# MAin.net
KiCad netlist of a schematic drawn in EAGLE
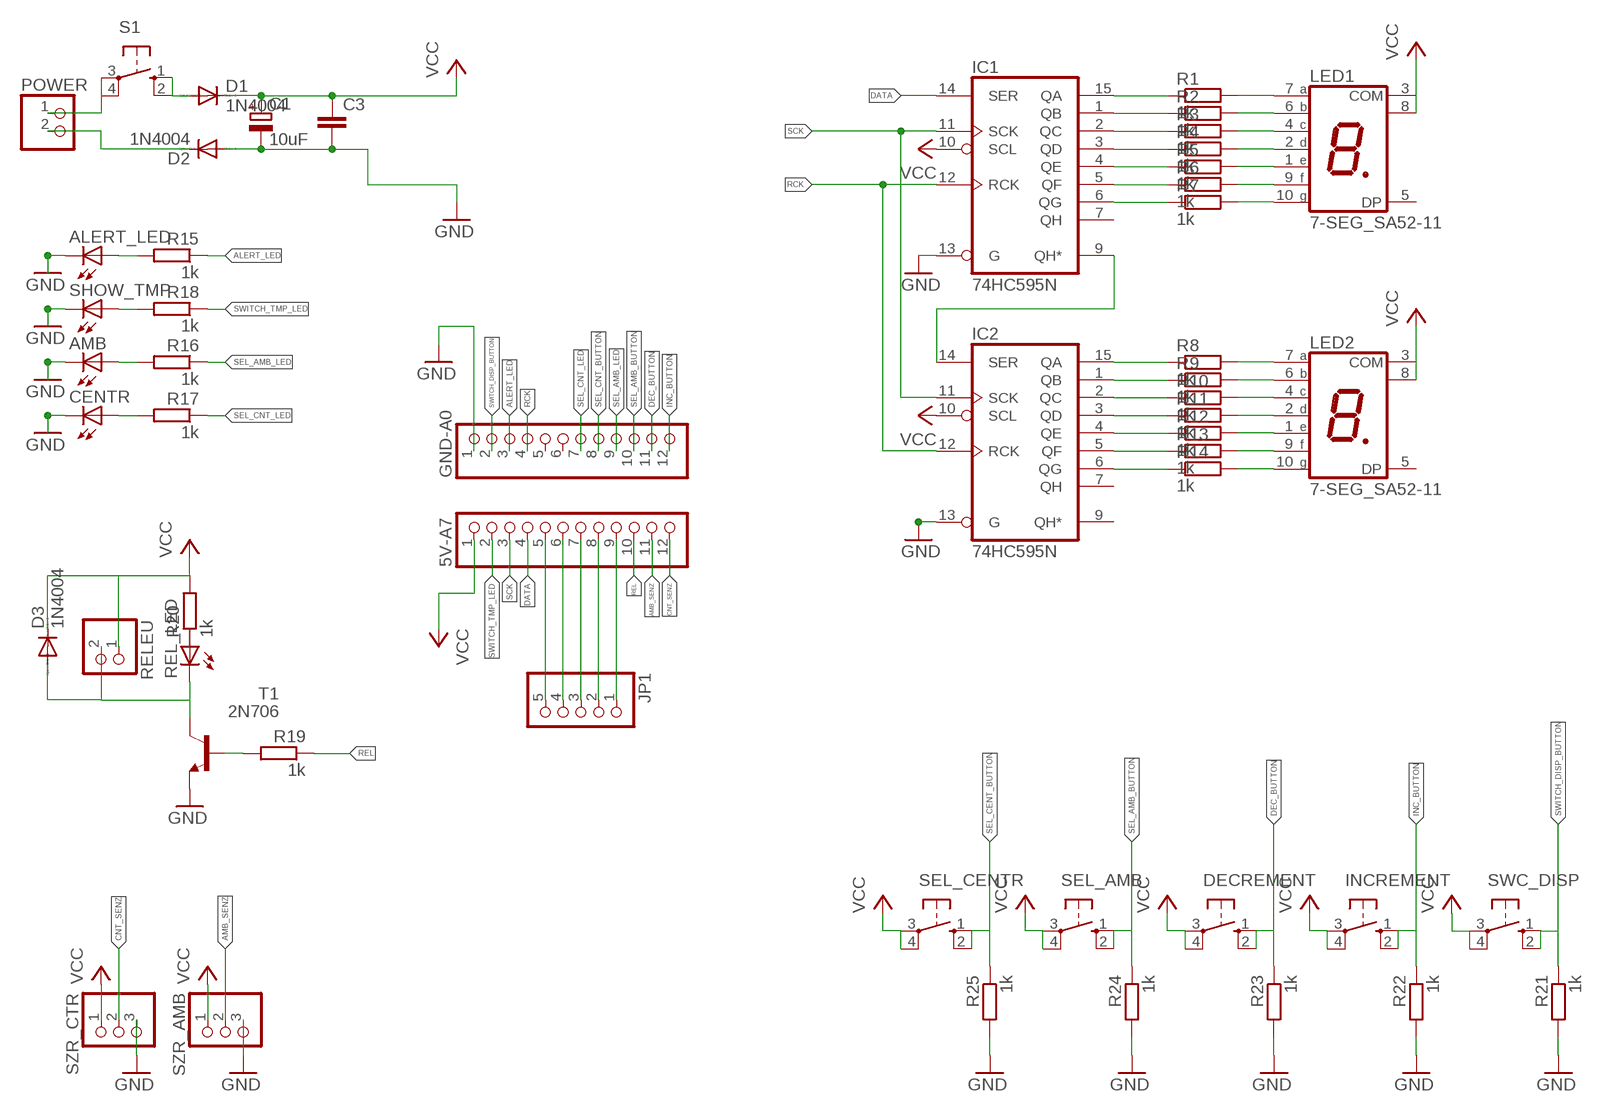
[diagram p0: schematic, sheet 1]

(export (version "E")
  (design (tool "Eeschema 10.0.6"))
  (components
    (comp (ref "5V-A7")
      (value "PINHD-1X12")
      (footprint "eagle-import:1X12")
      (libsource (lib "eagle-import") (part "PINHD-1X12"))
    )
    (comp (ref "ALERT_LED")
      (value "LED5MM")
      (footprint "eagle-import:LED5MM")
      (libsource (lib "eagle-import") (part "LED5MM"))
    )
    (comp (ref "AMB")
      (value "LED5MM")
      (footprint "eagle-import:LED5MM")
      (libsource (lib "eagle-import") (part "LED5MM"))
    )
    (comp (ref "C1")
      (value "10uF")
      (footprint "eagle-import:E2-5")
      (libsource (lib "eagle-import") (part "CPOL-EUE2-5"))
    )
    (comp (ref "C3")
      (value "C-EU025-024X044")
      (footprint "eagle-import:C025-024X044")
      (libsource (lib "eagle-import") (part "C-EU025-024X044"))
    )
    (comp (ref "CENTR")
      (value "LED5MM")
      (footprint "eagle-import:LED5MM")
      (libsource (lib "eagle-import") (part "LED5MM"))
    )
    (comp (ref "D1")
      (value "1N4004")
      (footprint "eagle-import:DO41-10")
      (libsource (lib "eagle-import") (part "1N4004"))
    )
    (comp (ref "D2")
      (value "1N4004")
      (footprint "eagle-import:DO41-10")
      (libsource (lib "eagle-import") (part "1N4004"))
    )
    (comp (ref "D3")
      (value "1N4004")
      (footprint "eagle-import:DO41-10")
      (libsource (lib "eagle-import") (part "1N4004"))
    )
    (comp (ref "DECREMENT")
      (value "40-XX")
      (footprint "eagle-import:B3F-40XX")
      (fields (field (name "MF") "OMRON COMPONENTS USA") (field (name "MPN") "B3F-4000"))
      (libsource (lib "eagle-import") (part "40-XX"))
    )
    (comp (ref "GND-A0")
      (value "PINHD-1X12")
      (footprint "eagle-import:1X12")
      (libsource (lib "eagle-import") (part "PINHD-1X12"))
    )
    (comp (ref "IC1")
      (value "74HC595N")
      (footprint "eagle-import:DIL16")
      (libsource (lib "eagle-import") (part "74595NHC"))
    )
    (comp (ref "IC2")
      (value "74HC595N")
      (footprint "eagle-import:DIL16")
      (libsource (lib "eagle-import") (part "74595NHC"))
    )
    (comp (ref "INCREMENT")
      (value "40-XX")
      (footprint "eagle-import:B3F-40XX")
      (fields (field (name "MF") "OMRON COMPONENTS USA") (field (name "MPN") "B3F-4000"))
      (libsource (lib "eagle-import") (part "40-XX"))
    )
    (comp (ref "JP1")
      (value "PINHD-1X5")
      (footprint "eagle-import:1X05")
      (libsource (lib "eagle-import") (part "PINHD-1X5"))
    )
    (comp (ref "LED1")
      (value "7-SEG_SA52-11")
      (footprint "eagle-import:SA52-11")
      (libsource (lib "eagle-import") (part "7-SEG_SA52-11"))
    )
    (comp (ref "LED2")
      (value "7-SEG_SA52-11")
      (footprint "eagle-import:SA52-11")
      (libsource (lib "eagle-import") (part "7-SEG_SA52-11"))
    )
    (comp (ref "POWER")
      (value "PINHD-1X2")
      (footprint "eagle-import:1X02")
      (libsource (lib "eagle-import") (part "PINHD-1X2"))
    )
    (comp (ref "R1")
      (value "1k")
      (footprint "eagle-import:0309_12")
      (libsource (lib "eagle-import") (part "R-EU_0309/12"))
    )
    (comp (ref "R2")
      (value "1k")
      (footprint "eagle-import:0309_12")
      (libsource (lib "eagle-import") (part "R-EU_0309/12"))
    )
    (comp (ref "R3")
      (value "1k")
      (footprint "eagle-import:0309_12")
      (libsource (lib "eagle-import") (part "R-EU_0309/12"))
    )
    (comp (ref "R4")
      (value "1k")
      (footprint "eagle-import:0309_12")
      (libsource (lib "eagle-import") (part "R-EU_0309/12"))
    )
    (comp (ref "R5")
      (value "1k")
      (footprint "eagle-import:0309_12")
      (libsource (lib "eagle-import") (part "R-EU_0309/12"))
    )
    (comp (ref "R6")
      (value "1k")
      (footprint "eagle-import:0309_12")
      (libsource (lib "eagle-import") (part "R-EU_0309/12"))
    )
    (comp (ref "R7")
      (value "1k")
      (footprint "eagle-import:0309_12")
      (libsource (lib "eagle-import") (part "R-EU_0309/12"))
    )
    (comp (ref "R8")
      (value "1k")
      (footprint "eagle-import:0309_12")
      (libsource (lib "eagle-import") (part "R-EU_0309/12"))
    )
    (comp (ref "R9")
      (value "1k")
      (footprint "eagle-import:0309_12")
      (libsource (lib "eagle-import") (part "R-EU_0309/12"))
    )
    (comp (ref "R10")
      (value "1k")
      (footprint "eagle-import:0309_12")
      (libsource (lib "eagle-import") (part "R-EU_0309/12"))
    )
    (comp (ref "R11")
      (value "1k")
      (footprint "eagle-import:0309_12")
      (libsource (lib "eagle-import") (part "R-EU_0309/12"))
    )
    (comp (ref "R12")
      (value "1k")
      (footprint "eagle-import:0309_12")
      (libsource (lib "eagle-import") (part "R-EU_0309/12"))
    )
    (comp (ref "R13")
      (value "1k")
      (footprint "eagle-import:0309_12")
      (libsource (lib "eagle-import") (part "R-EU_0309/12"))
    )
    (comp (ref "R14")
      (value "1k")
      (footprint "eagle-import:0309_12")
      (libsource (lib "eagle-import") (part "R-EU_0309/12"))
    )
    (comp (ref "R15")
      (value "1k")
      (footprint "eagle-import:0309_12")
      (libsource (lib "eagle-import") (part "R-EU_0309/12"))
    )
    (comp (ref "R16")
      (value "1k")
      (footprint "eagle-import:0309_12")
      (libsource (lib "eagle-import") (part "R-EU_0309/12"))
    )
    (comp (ref "R17")
      (value "1k")
      (footprint "eagle-import:0309_12")
      (libsource (lib "eagle-import") (part "R-EU_0309/12"))
    )
    (comp (ref "R18")
      (value "1k")
      (footprint "eagle-import:0309_12")
      (libsource (lib "eagle-import") (part "R-EU_0309/12"))
    )
    (comp (ref "R19")
      (value "1k")
      (footprint "eagle-import:0309_12")
      (libsource (lib "eagle-import") (part "R-EU_0309/12"))
    )
    (comp (ref "R20")
      (value "1k")
      (footprint "eagle-import:0309_12")
      (libsource (lib "eagle-import") (part "R-EU_0309/12"))
    )
    (comp (ref "R21")
      (value "1k")
      (footprint "eagle-import:0309_12")
      (libsource (lib "eagle-import") (part "R-EU_0309/12"))
    )
    (comp (ref "R22")
      (value "1k")
      (footprint "eagle-import:0309_12")
      (libsource (lib "eagle-import") (part "R-EU_0309/12"))
    )
    (comp (ref "R23")
      (value "1k")
      (footprint "eagle-import:0309_12")
      (libsource (lib "eagle-import") (part "R-EU_0309/12"))
    )
    (comp (ref "R24")
      (value "1k")
      (footprint "eagle-import:0309_12")
      (libsource (lib "eagle-import") (part "R-EU_0309/12"))
    )
    (comp (ref "R25")
      (value "1k")
      (footprint "eagle-import:0309_12")
      (libsource (lib "eagle-import") (part "R-EU_0309/12"))
    )
    (comp (ref "RELEU")
      (value "PINHD-1X2")
      (footprint "eagle-import:1X02")
      (libsource (lib "eagle-import") (part "PINHD-1X2"))
    )
    (comp (ref "REL_LED")
      (value "LED5MM")
      (footprint "eagle-import:LED5MM")
      (libsource (lib "eagle-import") (part "LED5MM"))
    )
    (comp (ref "S1")
      (value "10-XX")
      (footprint "eagle-import:B3F-10XX")
      (fields (field (name "MPN") "B3F-1000"))
      (libsource (lib "eagle-import") (part "10-XX"))
    )
    (comp (ref "SEL_AMB")
      (value "40-XX")
      (footprint "eagle-import:B3F-40XX")
      (fields (field (name "MF") "OMRON COMPONENTS USA") (field (name "MPN") "B3F-4000"))
      (libsource (lib "eagle-import") (part "40-XX"))
    )
    (comp (ref "SEL_CENTR")
      (value "40-XX")
      (footprint "eagle-import:B3F-40XX")
      (fields (field (name "MF") "OMRON COMPONENTS USA") (field (name "MPN") "B3F-4000"))
      (libsource (lib "eagle-import") (part "40-XX"))
    )
    (comp (ref "SHOW_TMP")
      (value "LED5MM")
      (footprint "eagle-import:LED5MM")
      (libsource (lib "eagle-import") (part "LED5MM"))
    )
    (comp (ref "SWC_DISP")
      (value "40-XX")
      (footprint "eagle-import:B3F-40XX")
      (fields (field (name "MF") "OMRON COMPONENTS USA") (field (name "MPN") "B3F-4000"))
      (libsource (lib "eagle-import") (part "40-XX"))
    )
    (comp (ref "SZR_AMB")
      (value "PINHD-1X3")
      (footprint "eagle-import:1X03")
      (libsource (lib "eagle-import") (part "PINHD-1X3"))
    )
    (comp (ref "SZR_CTR")
      (value "PINHD-1X3")
      (footprint "eagle-import:1X03")
      (libsource (lib "eagle-import") (part "PINHD-1X3"))
    )
    (comp (ref "T1")
      (value "2N706")
      (footprint "eagle-import:TO18")
      (libsource (lib "eagle-import") (part "2N706"))
    )
  )
  (nets
    (net (code "1") (name "ALERT_LED") (class "Default")
      (node (ref "GND-A0") (pin "3") (pinfunction "3_3") (pintype "passive"))
      (node (ref "R15") (pin "1") (pinfunction "1_1") (pintype "passive"))
    )
    (net (code "2") (name "AMB_SENZ") (class "Default")
      (node (ref "5V-A7") (pin "11") (pinfunction "11_11") (pintype "passive"))
      (node (ref "SZR_AMB") (pin "2") (pinfunction "2_2") (pintype "passive"))
    )
    (net (code "3") (name "CNT_SENZ") (class "Default")
      (node (ref "5V-A7") (pin "12") (pinfunction "12_12") (pintype "passive"))
      (node (ref "SZR_CTR") (pin "2") (pinfunction "2_2") (pintype "passive"))
    )
    (net (code "4") (name "DATA") (class "Default")
      (node (ref "5V-A7") (pin "4") (pinfunction "4_4") (pintype "passive"))
      (node (ref "IC1") (pin "14") (pinfunction "SER_14") (pintype "input"))
    )
    (net (code "5") (name "DEC_BUTTON") (class "Default")
      (node (ref "DECREMENT") (pin "1") (pinfunction "S_1") (pintype "passive"))
      (node (ref "DECREMENT") (pin "2") (pinfunction "S1_2") (pintype "passive"))
      (node (ref "GND-A0") (pin "11") (pinfunction "11_11") (pintype "passive"))
      (node (ref "R23") (pin "1") (pinfunction "1_1") (pintype "passive"))
    )
    (net (code "6") (name "GND") (class "Default")
      (node (ref "ALERT_LED") (pin "K") (pinfunction "C_K") (pintype "passive"))
      (node (ref "AMB") (pin "K") (pinfunction "C_K") (pintype "passive"))
      (node (ref "C1") (pin "-") (pinfunction "-_-") (pintype "passive"))
      (node (ref "C3") (pin "2") (pinfunction "2_2") (pintype "passive"))
      (node (ref "CENTR") (pin "K") (pinfunction "C_K") (pintype "passive"))
      (node (ref "D2") (pin "A") (pinfunction "A_A") (pintype "passive"))
      (node (ref "GND-A0") (pin "1") (pinfunction "1_1") (pintype "passive"))
      (node (ref "IC1") (pin "13") (pinfunction "G_13") (pintype "input"))
      (node (ref "IC2") (pin "13") (pinfunction "G_13") (pintype "input"))
      (node (ref "R21") (pin "2") (pinfunction "2_2") (pintype "passive"))
      (node (ref "R22") (pin "2") (pinfunction "2_2") (pintype "passive"))
      (node (ref "R23") (pin "2") (pinfunction "2_2") (pintype "passive"))
      (node (ref "R24") (pin "2") (pinfunction "2_2") (pintype "passive"))
      (node (ref "R25") (pin "2") (pinfunction "2_2") (pintype "passive"))
      (node (ref "SHOW_TMP") (pin "K") (pinfunction "C_K") (pintype "passive"))
      (node (ref "SZR_AMB") (pin "3") (pinfunction "3_3") (pintype "passive"))
      (node (ref "SZR_CTR") (pin "3") (pinfunction "3_3") (pintype "passive"))
      (node (ref "T1") (pin "1") (pinfunction "E_1") (pintype "passive"))
    )
    (net (code "7") (name "INC_BUTTON") (class "Default")
      (node (ref "GND-A0") (pin "12") (pinfunction "12_12") (pintype "passive"))
      (node (ref "INCREMENT") (pin "1") (pinfunction "S_1") (pintype "passive"))
      (node (ref "INCREMENT") (pin "2") (pinfunction "S1_2") (pintype "passive"))
      (node (ref "R22") (pin "1") (pinfunction "1_1") (pintype "passive"))
    )
    (net (code "8") (name "Net-(5V-A7-Pad5)") (class "Default")
      (node (ref "5V-A7") (pin "5") (pinfunction "5_5") (pintype "passive"))
      (node (ref "JP1") (pin "5") (pinfunction "5_5") (pintype "passive"))
    )
    (net (code "9") (name "Net-(5V-A7-Pad6)") (class "Default")
      (node (ref "5V-A7") (pin "6") (pinfunction "6_6") (pintype "passive"))
      (node (ref "JP1") (pin "4") (pinfunction "4_4") (pintype "passive"))
    )
    (net (code "10") (name "Net-(5V-A7-Pad7)") (class "Default")
      (node (ref "5V-A7") (pin "7") (pinfunction "7_7") (pintype "passive"))
      (node (ref "JP1") (pin "3") (pinfunction "3_3") (pintype "passive"))
    )
    (net (code "11") (name "Net-(5V-A7-Pad8)") (class "Default")
      (node (ref "5V-A7") (pin "8") (pinfunction "8_8") (pintype "passive"))
      (node (ref "JP1") (pin "2") (pinfunction "2_2") (pintype "passive"))
    )
    (net (code "12") (name "Net-(5V-A7-Pad9)") (class "Default")
      (node (ref "5V-A7") (pin "9") (pinfunction "9_9") (pintype "passive"))
      (node (ref "JP1") (pin "1") (pinfunction "1_1") (pintype "passive"))
    )
    (net (code "13") (name "Net-(ALERT_LED-PadA)") (class "Default")
      (node (ref "ALERT_LED") (pin "A") (pinfunction "A_A") (pintype "passive"))
      (node (ref "R15") (pin "2") (pinfunction "2_2") (pintype "passive"))
    )
    (net (code "14") (name "Net-(AMB-PadA)") (class "Default")
      (node (ref "AMB") (pin "A") (pinfunction "A_A") (pintype "passive"))
      (node (ref "R16") (pin "2") (pinfunction "2_2") (pintype "passive"))
    )
    (net (code "15") (name "Net-(CENTR-PadA)") (class "Default")
      (node (ref "CENTR") (pin "A") (pinfunction "A_A") (pintype "passive"))
      (node (ref "R17") (pin "2") (pinfunction "2_2") (pintype "passive"))
    )
    (net (code "16") (name "Net-(D2-PadC)") (class "Default")
      (node (ref "D2") (pin "C") (pinfunction "C_C") (pintype "passive"))
      (node (ref "POWER") (pin "2") (pinfunction "2_2") (pintype "passive"))
    )
    (net (code "17") (name "Net-(IC1A-QA)") (class "Default")
      (node (ref "IC1") (pin "15") (pinfunction "QA_15") (pintype "tri_state"))
      (node (ref "R1") (pin "1") (pinfunction "1_1") (pintype "passive"))
    )
    (net (code "18") (name "Net-(IC1A-QB)") (class "Default")
      (node (ref "IC1") (pin "1") (pinfunction "QB_1") (pintype "tri_state"))
      (node (ref "R2") (pin "1") (pinfunction "1_1") (pintype "passive"))
    )
    (net (code "19") (name "Net-(IC1A-QC)") (class "Default")
      (node (ref "IC1") (pin "2") (pinfunction "QC_2") (pintype "tri_state"))
      (node (ref "R3") (pin "1") (pinfunction "1_1") (pintype "passive"))
    )
    (net (code "20") (name "Net-(IC1A-QD)") (class "Default")
      (node (ref "IC1") (pin "3") (pinfunction "QD_3") (pintype "tri_state"))
      (node (ref "R4") (pin "1") (pinfunction "1_1") (pintype "passive"))
    )
    (net (code "21") (name "Net-(IC1A-QE)") (class "Default")
      (node (ref "IC1") (pin "4") (pinfunction "QE_4") (pintype "tri_state"))
      (node (ref "R5") (pin "1") (pinfunction "1_1") (pintype "passive"))
    )
    (net (code "22") (name "Net-(IC1A-QF)") (class "Default")
      (node (ref "IC1") (pin "5") (pinfunction "QF_5") (pintype "tri_state"))
      (node (ref "R6") (pin "1") (pinfunction "1_1") (pintype "passive"))
    )
    (net (code "23") (name "Net-(IC1A-QG)") (class "Default")
      (node (ref "IC1") (pin "6") (pinfunction "QG_6") (pintype "tri_state"))
      (node (ref "R7") (pin "1") (pinfunction "1_1") (pintype "passive"))
    )
    (net (code "24") (name "Net-(IC1A-QH*)") (class "Default")
      (node (ref "IC1") (pin "9") (pinfunction "QH*_9") (pintype "tri_state"))
      (node (ref "IC2") (pin "14") (pinfunction "SER_14") (pintype "input"))
    )
    (net (code "25") (name "Net-(IC2A-QA)") (class "Default")
      (node (ref "IC2") (pin "15") (pinfunction "QA_15") (pintype "tri_state"))
      (node (ref "R8") (pin "1") (pinfunction "1_1") (pintype "passive"))
    )
    (net (code "26") (name "Net-(IC2A-QB)") (class "Default")
      (node (ref "IC2") (pin "1") (pinfunction "QB_1") (pintype "tri_state"))
      (node (ref "R9") (pin "1") (pinfunction "1_1") (pintype "passive"))
    )
    (net (code "27") (name "Net-(IC2A-QC)") (class "Default")
      (node (ref "IC2") (pin "2") (pinfunction "QC_2") (pintype "tri_state"))
      (node (ref "R10") (pin "1") (pinfunction "1_1") (pintype "passive"))
    )
    (net (code "28") (name "Net-(IC2A-QD)") (class "Default")
      (node (ref "IC2") (pin "3") (pinfunction "QD_3") (pintype "tri_state"))
      (node (ref "R11") (pin "1") (pinfunction "1_1") (pintype "passive"))
    )
    (net (code "29") (name "Net-(IC2A-QE)") (class "Default")
      (node (ref "IC2") (pin "4") (pinfunction "QE_4") (pintype "tri_state"))
      (node (ref "R12") (pin "1") (pinfunction "1_1") (pintype "passive"))
    )
    (net (code "30") (name "Net-(IC2A-QF)") (class "Default")
      (node (ref "IC2") (pin "5") (pinfunction "QF_5") (pintype "tri_state"))
      (node (ref "R13") (pin "1") (pinfunction "1_1") (pintype "passive"))
    )
    (net (code "31") (name "Net-(IC2A-QG)") (class "Default")
      (node (ref "IC2") (pin "6") (pinfunction "QG_6") (pintype "tri_state"))
      (node (ref "R14") (pin "1") (pinfunction "1_1") (pintype "passive"))
    )
    (net (code "32") (name "Net-(LED1-A)") (class "Default")
      (node (ref "LED1") (pin "7") (pinfunction "A_7") (pintype "passive"))
      (node (ref "R1") (pin "2") (pinfunction "2_2") (pintype "passive"))
    )
    (net (code "33") (name "Net-(LED1-B)") (class "Default")
      (node (ref "LED1") (pin "6") (pinfunction "B_6") (pintype "passive"))
      (node (ref "R2") (pin "2") (pinfunction "2_2") (pintype "passive"))
    )
    (net (code "34") (name "Net-(LED1-C)") (class "Default")
      (node (ref "LED1") (pin "4") (pinfunction "C_4") (pintype "passive"))
      (node (ref "R3") (pin "2") (pinfunction "2_2") (pintype "passive"))
    )
    (net (code "35") (name "Net-(LED1-D)") (class "Default")
      (node (ref "LED1") (pin "2") (pinfunction "D_2") (pintype "passive"))
      (node (ref "R4") (pin "2") (pinfunction "2_2") (pintype "passive"))
    )
    (net (code "36") (name "Net-(LED1-E)") (class "Default")
      (node (ref "LED1") (pin "1") (pinfunction "E_1") (pintype "passive"))
      (node (ref "R5") (pin "2") (pinfunction "2_2") (pintype "passive"))
    )
    (net (code "37") (name "Net-(LED1-F)") (class "Default")
      (node (ref "LED1") (pin "9") (pinfunction "F_9") (pintype "passive"))
      (node (ref "R6") (pin "2") (pinfunction "2_2") (pintype "passive"))
    )
    (net (code "38") (name "Net-(LED1-G)") (class "Default")
      (node (ref "LED1") (pin "10") (pinfunction "G_10") (pintype "passive"))
      (node (ref "R7") (pin "2") (pinfunction "2_2") (pintype "passive"))
    )
    (net (code "39") (name "Net-(LED2-A)") (class "Default")
      (node (ref "LED2") (pin "7") (pinfunction "A_7") (pintype "passive"))
      (node (ref "R8") (pin "2") (pinfunction "2_2") (pintype "passive"))
    )
    (net (code "40") (name "Net-(LED2-B)") (class "Default")
      (node (ref "LED2") (pin "6") (pinfunction "B_6") (pintype "passive"))
      (node (ref "R9") (pin "2") (pinfunction "2_2") (pintype "passive"))
    )
    (net (code "41") (name "Net-(LED2-C)") (class "Default")
      (node (ref "LED2") (pin "4") (pinfunction "C_4") (pintype "passive"))
      (node (ref "R10") (pin "2") (pinfunction "2_2") (pintype "passive"))
    )
    (net (code "42") (name "Net-(LED2-D)") (class "Default")
      (node (ref "LED2") (pin "2") (pinfunction "D_2") (pintype "passive"))
      (node (ref "R11") (pin "2") (pinfunction "2_2") (pintype "passive"))
    )
    (net (code "43") (name "Net-(LED2-E)") (class "Default")
      (node (ref "LED2") (pin "1") (pinfunction "E_1") (pintype "passive"))
      (node (ref "R12") (pin "2") (pinfunction "2_2") (pintype "passive"))
    )
    (net (code "44") (name "Net-(LED2-F)") (class "Default")
      (node (ref "LED2") (pin "9") (pinfunction "F_9") (pintype "passive"))
      (node (ref "R13") (pin "2") (pinfunction "2_2") (pintype "passive"))
    )
    (net (code "45") (name "Net-(LED2-G)") (class "Default")
      (node (ref "LED2") (pin "10") (pinfunction "G_10") (pintype "passive"))
      (node (ref "R14") (pin "2") (pinfunction "2_2") (pintype "passive"))
    )
    (net (code "46") (name "Net-(R18-Pad2)") (class "Default")
      (node (ref "R18") (pin "2") (pinfunction "2_2") (pintype "passive"))
      (node (ref "SHOW_TMP") (pin "A") (pinfunction "A_A") (pintype "passive"))
    )
    (net (code "47") (name "Net-(R20-Pad1)") (class "Default")
      (node (ref "R20") (pin "1") (pinfunction "1_1") (pintype "passive"))
      (node (ref "REL_LED") (pin "A") (pinfunction "A_A") (pintype "passive"))
    )
    (net (code "48") (name "Net-(REL_LED-C)") (class "Default")
      (node (ref "D3") (pin "A") (pinfunction "A_A") (pintype "passive"))
      (node (ref "RELEU") (pin "2") (pinfunction "2_2") (pintype "passive"))
      (node (ref "REL_LED") (pin "K") (pinfunction "C_K") (pintype "passive"))
      (node (ref "T1") (pin "3") (pinfunction "C_3") (pintype "passive"))
    )
    (net (code "49") (name "Net-(S1-P)") (class "Default")
      (node (ref "POWER") (pin "1") (pinfunction "1_1") (pintype "passive"))
      (node (ref "S1") (pin "3") (pinfunction "P_3") (pintype "passive"))
      (node (ref "S1") (pin "4") (pinfunction "P1_4") (pintype "passive"))
    )
    (net (code "50") (name "Net-(S1-S)") (class "Default")
      (node (ref "D1") (pin "A") (pinfunction "A_A") (pintype "passive"))
      (node (ref "S1") (pin "1") (pinfunction "S_1") (pintype "passive"))
      (node (ref "S1") (pin "2") (pinfunction "S1_2") (pintype "passive"))
    )
    (net (code "51") (name "Net-(T1-B)") (class "Default")
      (node (ref "R19") (pin "2") (pinfunction "2_2") (pintype "passive"))
      (node (ref "T1") (pin "2") (pinfunction "B_2") (pintype "passive"))
    )
    (net (code "52") (name "RCK") (class "Default")
      (node (ref "GND-A0") (pin "4") (pinfunction "4_4") (pintype "passive"))
      (node (ref "IC1") (pin "12") (pinfunction "RCK_12") (pintype "input"))
      (node (ref "IC2") (pin "12") (pinfunction "RCK_12") (pintype "input"))
    )
    (net (code "53") (name "REL") (class "Default")
      (node (ref "5V-A7") (pin "10") (pinfunction "10_10") (pintype "passive"))
      (node (ref "R19") (pin "1") (pinfunction "1_1") (pintype "passive"))
    )
    (net (code "54") (name "SCK") (class "Default")
      (node (ref "5V-A7") (pin "3") (pinfunction "3_3") (pintype "passive"))
      (node (ref "IC1") (pin "11") (pinfunction "SCK_11") (pintype "input"))
      (node (ref "IC2") (pin "11") (pinfunction "SCK_11") (pintype "input"))
    )
    (net (code "55") (name "SEL_AMB_BUTTON") (class "Default")
      (node (ref "GND-A0") (pin "10") (pinfunction "10_10") (pintype "passive"))
      (node (ref "R24") (pin "1") (pinfunction "1_1") (pintype "passive"))
      (node (ref "SEL_AMB") (pin "1") (pinfunction "S_1") (pintype "passive"))
      (node (ref "SEL_AMB") (pin "2") (pinfunction "S1_2") (pintype "passive"))
    )
    (net (code "56") (name "SEL_AMB_LED") (class "Default")
      (node (ref "GND-A0") (pin "9") (pinfunction "9_9") (pintype "passive"))
      (node (ref "R16") (pin "1") (pinfunction "1_1") (pintype "passive"))
    )
    (net (code "57") (name "SEL_CENT_BUTTON") (class "Default")
      (node (ref "GND-A0") (pin "7") (pinfunction "7_7") (pintype "passive"))
      (node (ref "R25") (pin "1") (pinfunction "1_1") (pintype "passive"))
      (node (ref "SEL_CENTR") (pin "1") (pinfunction "S_1") (pintype "passive"))
      (node (ref "SEL_CENTR") (pin "2") (pinfunction "S1_2") (pintype "passive"))
    )
    (net (code "58") (name "SEL_CNT_BUTTON") (class "Default")
      (node (ref "GND-A0") (pin "8") (pinfunction "8_8") (pintype "passive"))
    )
    (net (code "59") (name "SEL_CNT_LED") (class "Default")
      (node (ref "R17") (pin "1") (pinfunction "1_1") (pintype "passive"))
    )
    (net (code "60") (name "SWITCH_DISP_BUTTON") (class "Default")
      (node (ref "GND-A0") (pin "2") (pinfunction "2_2") (pintype "passive"))
      (node (ref "R21") (pin "1") (pinfunction "1_1") (pintype "passive"))
      (node (ref "SWC_DISP") (pin "1") (pinfunction "S_1") (pintype "passive"))
      (node (ref "SWC_DISP") (pin "2") (pinfunction "S1_2") (pintype "passive"))
    )
    (net (code "61") (name "SWITCH_TMP_LED") (class "Default")
      (node (ref "5V-A7") (pin "2") (pinfunction "2_2") (pintype "passive"))
      (node (ref "R18") (pin "1") (pinfunction "1_1") (pintype "passive"))
    )
    (net (code "62") (name "VCC") (class "Default")
      (node (ref "5V-A7") (pin "1") (pinfunction "1_1") (pintype "passive"))
      (node (ref "C1") (pin "+") (pinfunction "+_+") (pintype "passive"))
      (node (ref "C3") (pin "1") (pinfunction "1_1") (pintype "passive"))
      (node (ref "D1") (pin "C") (pinfunction "C_C") (pintype "passive"))
      (node (ref "D3") (pin "C") (pinfunction "C_C") (pintype "passive"))
      (node (ref "DECREMENT") (pin "3") (pinfunction "P_3") (pintype "passive"))
      (node (ref "DECREMENT") (pin "4") (pinfunction "P1_4") (pintype "passive"))
      (node (ref "IC1") (pin "10") (pinfunction "SCL_10") (pintype "input"))
      (node (ref "IC2") (pin "10") (pinfunction "SCL_10") (pintype "input"))
      (node (ref "INCREMENT") (pin "3") (pinfunction "P_3") (pintype "passive"))
      (node (ref "INCREMENT") (pin "4") (pinfunction "P1_4") (pintype "passive"))
      (node (ref "LED1") (pin "3") (pinfunction "COM_3") (pintype "passive"))
      (node (ref "LED1") (pin "8") (pinfunction "COM_8") (pintype "passive"))
      (node (ref "LED2") (pin "3") (pinfunction "COM_3") (pintype "passive"))
      (node (ref "LED2") (pin "8") (pinfunction "COM_8") (pintype "passive"))
      (node (ref "R20") (pin "2") (pinfunction "2_2") (pintype "passive"))
      (node (ref "RELEU") (pin "1") (pinfunction "1_1") (pintype "passive"))
      (node (ref "SEL_AMB") (pin "3") (pinfunction "P_3") (pintype "passive"))
      (node (ref "SEL_AMB") (pin "4") (pinfunction "P1_4") (pintype "passive"))
      (node (ref "SEL_CENTR") (pin "3") (pinfunction "P_3") (pintype "passive"))
      (node (ref "SEL_CENTR") (pin "4") (pinfunction "P1_4") (pintype "passive"))
      (node (ref "SWC_DISP") (pin "3") (pinfunction "P_3") (pintype "passive"))
      (node (ref "SWC_DISP") (pin "4") (pinfunction "P1_4") (pintype "passive"))
      (node (ref "SZR_AMB") (pin "1") (pinfunction "1_1") (pintype "passive"))
      (node (ref "SZR_CTR") (pin "1") (pinfunction "1_1") (pintype "passive"))
    )
    (net (code "63") (name "unconnected-(GND-A0-Pad5)") (class "Default")
      (node (ref "GND-A0") (pin "5") (pinfunction "5_5") (pintype "passive"))
    )
    (net (code "64") (name "unconnected-(GND-A0-Pad6)") (class "Default")
      (node (ref "GND-A0") (pin "6") (pinfunction "6_6") (pintype "passive"))
    )
    (net (code "65") (name "unconnected-(IC1A-QH-Pad7)") (class "Default")
      (node (ref "IC1") (pin "7") (pinfunction "QH_7") (pintype "tri_state"))
    )
    (net (code "66") (name "unconnected-(IC2A-QH*-Pad9)") (class "Default")
      (node (ref "IC2") (pin "9") (pinfunction "QH*_9") (pintype "tri_state"))
    )
    (net (code "67") (name "unconnected-(IC2A-QH-Pad7)") (class "Default")
      (node (ref "IC2") (pin "7") (pinfunction "QH_7") (pintype "tri_state"))
    )
    (net (code "68") (name "unconnected-(LED1-DP-Pad5)") (class "Default")
      (node (ref "LED1") (pin "5") (pinfunction "DP_5") (pintype "passive"))
    )
    (net (code "69") (name "unconnected-(LED2-DP-Pad5)") (class "Default")
      (node (ref "LED2") (pin "5") (pinfunction "DP_5") (pintype "passive"))
    )
  )
)
